# SCH_macropad_2024-06-17.net
KiCad netlist of a schematic drawn in EasyEDA
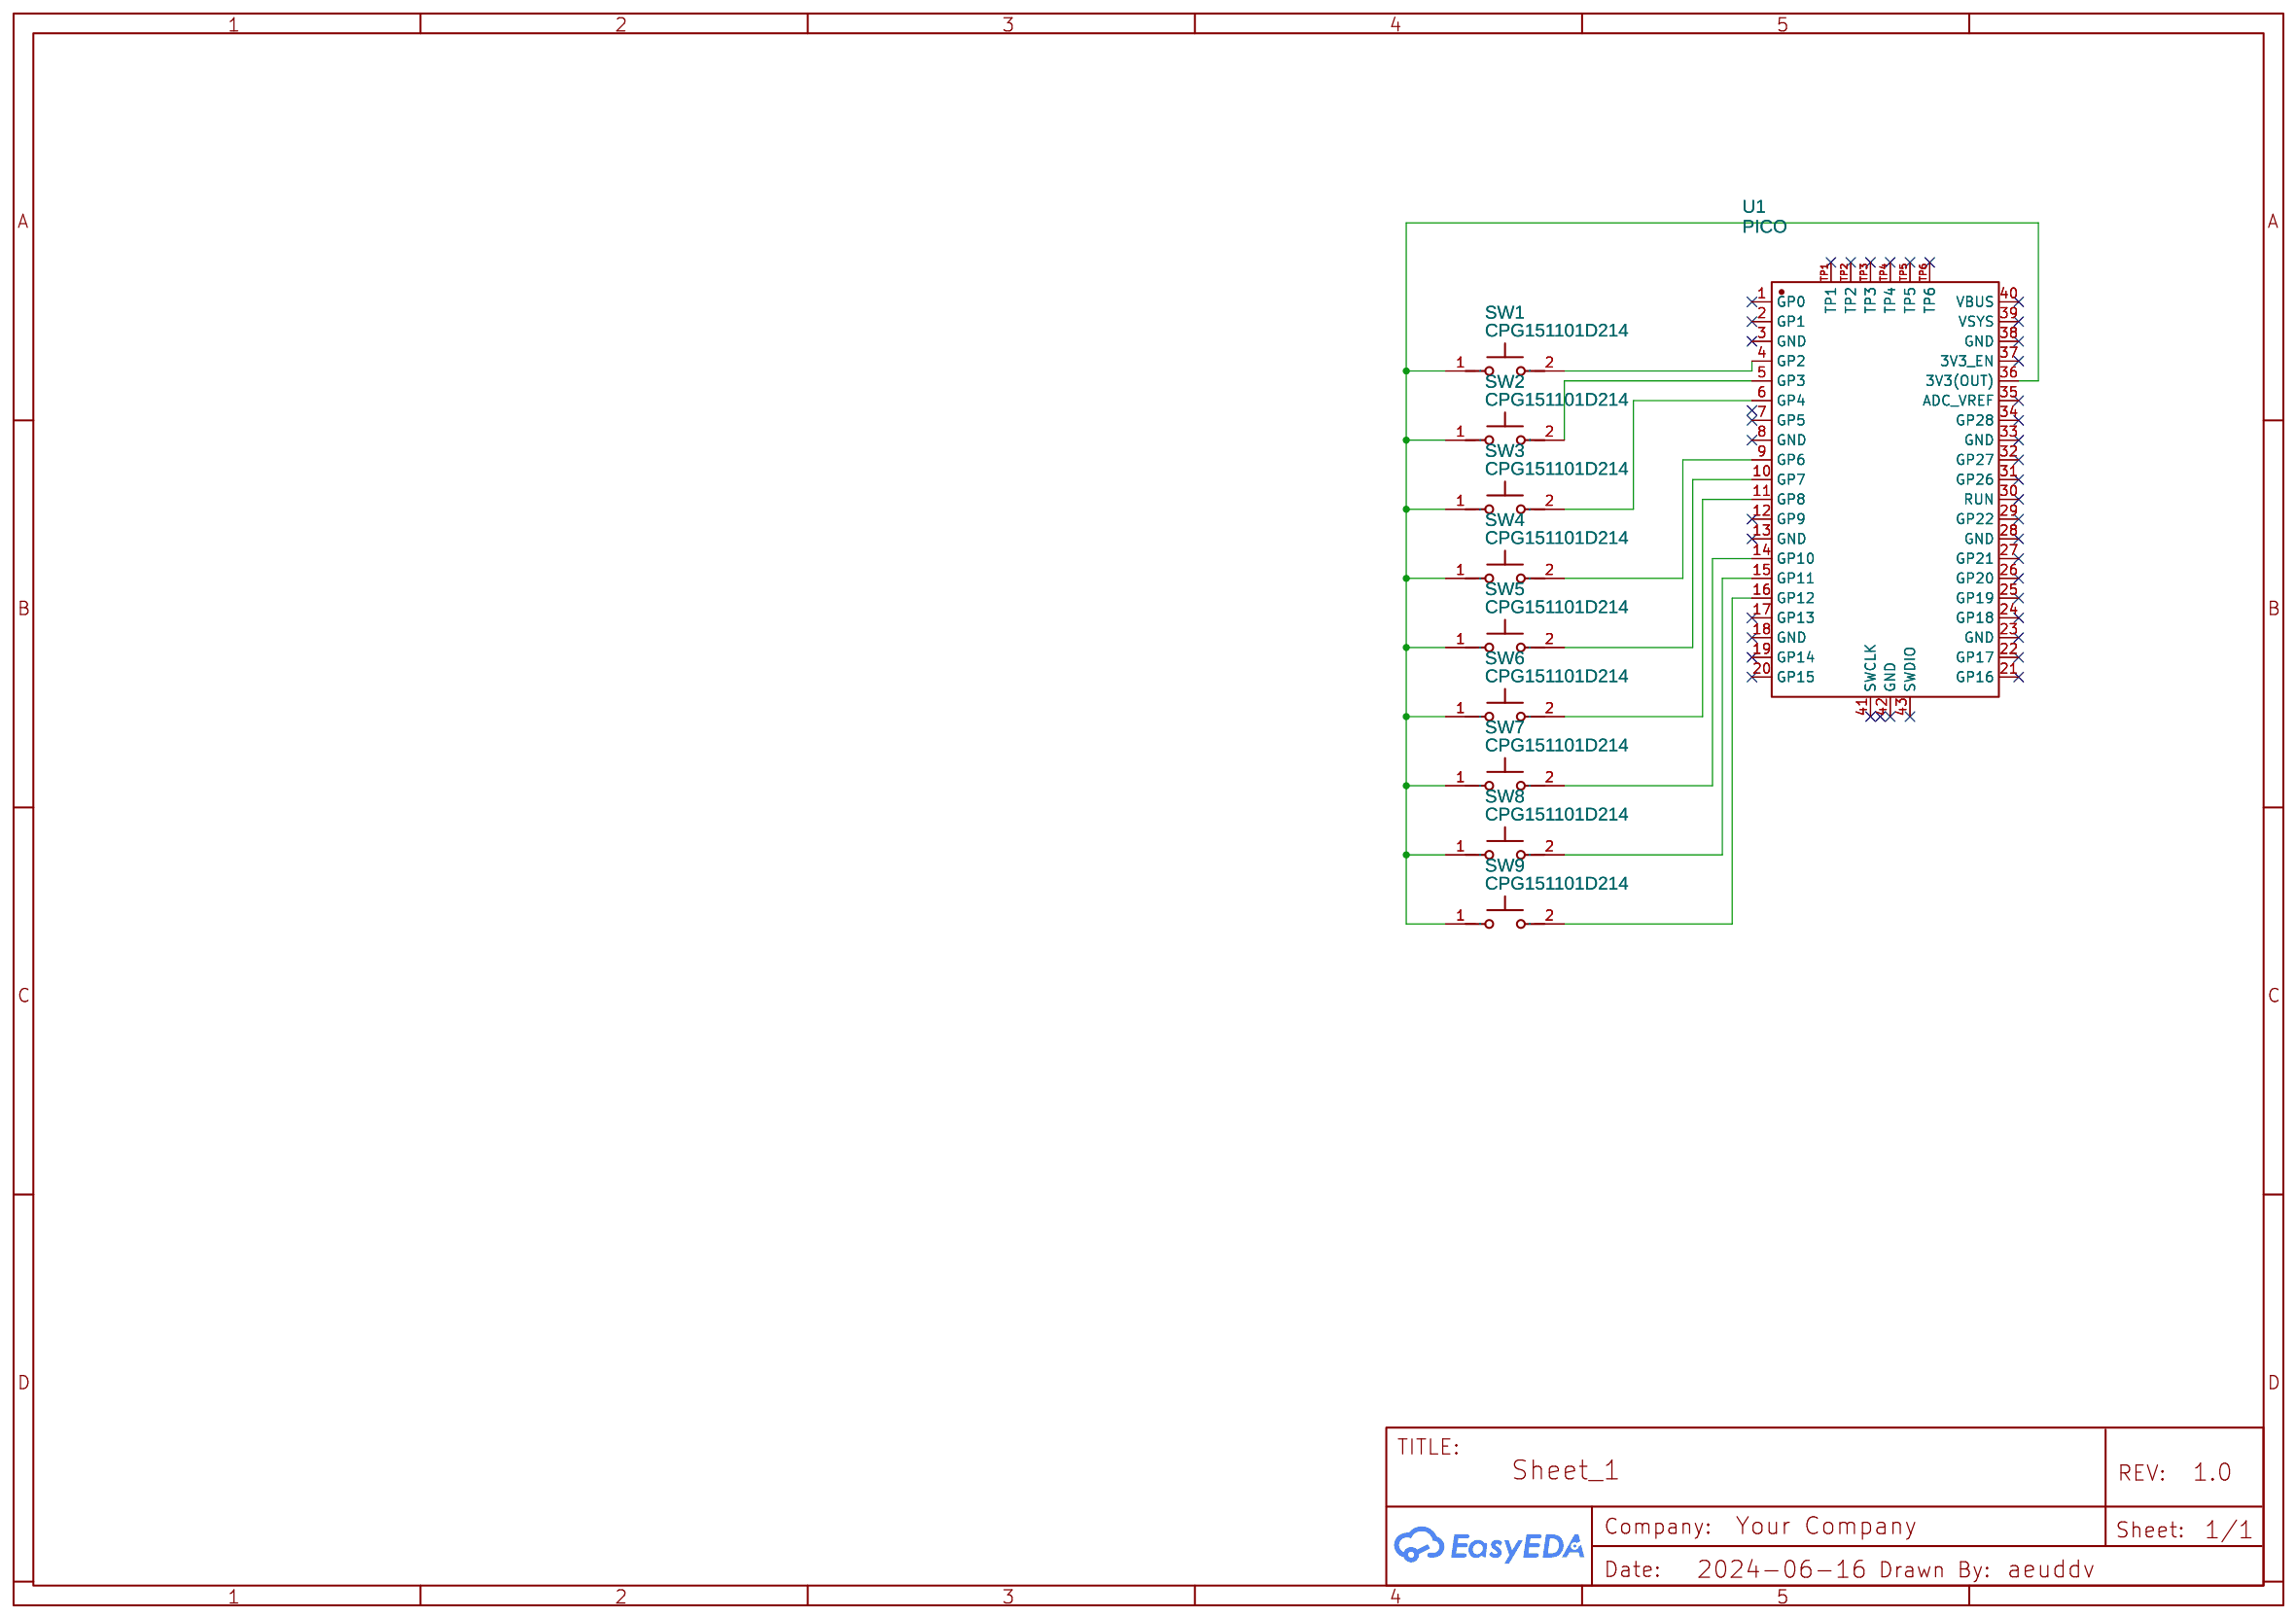
[diagram p0: schematic sheet]

(export (version "E")
  (design (tool "Eeschema 10.0.6"))
  (components
    (comp (ref "SW1")
      (value "CPG151101D214")
      (fields (field (name "Manufacturer") "Kailh(凯华)"))
      (libsource (lib "") (part "CPG151101D214"))
    )
    (comp (ref "SW2")
      (value "CPG151101D214")
      (fields (field (name "Manufacturer") "Kailh(凯华)"))
      (libsource (lib "") (part "CPG151101D214"))
    )
    (comp (ref "SW3")
      (value "CPG151101D214")
      (fields (field (name "Manufacturer") "Kailh(凯华)"))
      (libsource (lib "") (part "CPG151101D214"))
    )
    (comp (ref "SW4")
      (value "CPG151101D214")
      (fields (field (name "Manufacturer") "Kailh(凯华)"))
      (libsource (lib "") (part "CPG151101D214"))
    )
    (comp (ref "SW5")
      (value "CPG151101D214")
      (fields (field (name "Manufacturer") "Kailh(凯华)"))
      (libsource (lib "") (part "CPG151101D214"))
    )
    (comp (ref "SW6")
      (value "CPG151101D214")
      (fields (field (name "Manufacturer") "Kailh(凯华)"))
      (libsource (lib "") (part "CPG151101D214"))
    )
    (comp (ref "SW7")
      (value "CPG151101D214")
      (fields (field (name "Manufacturer") "Kailh(凯华)"))
      (libsource (lib "") (part "CPG151101D214"))
    )
    (comp (ref "SW8")
      (value "CPG151101D214")
      (fields (field (name "Manufacturer") "Kailh(凯华)"))
      (libsource (lib "") (part "CPG151101D214"))
    )
    (comp (ref "SW9")
      (value "CPG151101D214")
      (fields (field (name "Manufacturer") "Kailh(凯华)"))
      (libsource (lib "") (part "CPG151101D214"))
    )
    (comp (ref "U1")
      (value "PICO")
      (fields (field (name "Manufacturer") "Raspberry Pi(树莓派)"))
      (libsource (lib "") (part "PICO"))
    )
  )
  (nets
    (net (code "1") (name "Net-(U1-3V3(OUT))") (class "Default")
      (node (ref "SW1") (pin "1") (pinfunction "1_1") (pintype "unspecified"))
      (node (ref "SW2") (pin "1") (pinfunction "1_1") (pintype "unspecified"))
      (node (ref "SW3") (pin "1") (pinfunction "1_1") (pintype "unspecified"))
      (node (ref "SW4") (pin "1") (pinfunction "1_1") (pintype "unspecified"))
      (node (ref "SW5") (pin "1") (pinfunction "1_1") (pintype "unspecified"))
      (node (ref "SW6") (pin "1") (pinfunction "1_1") (pintype "unspecified"))
      (node (ref "SW7") (pin "1") (pinfunction "1_1") (pintype "unspecified"))
      (node (ref "SW8") (pin "1") (pinfunction "1_1") (pintype "unspecified"))
      (node (ref "SW9") (pin "1") (pinfunction "1_1") (pintype "unspecified"))
      (node (ref "U1") (pin "36") (pinfunction "3V3(OUT)_36") (pintype "unspecified"))
    )
    (net (code "2") (name "Net-(U1-GP2)") (class "Default")
      (node (ref "SW1") (pin "2") (pinfunction "2_2") (pintype "unspecified"))
      (node (ref "U1") (pin "4") (pinfunction "GP2_4") (pintype "unspecified"))
    )
    (net (code "3") (name "Net-(U1-GP3)") (class "Default")
      (node (ref "SW2") (pin "2") (pinfunction "2_2") (pintype "unspecified"))
      (node (ref "U1") (pin "5") (pinfunction "GP3_5") (pintype "unspecified"))
    )
    (net (code "4") (name "Net-(U1-GP4)") (class "Default")
      (node (ref "SW3") (pin "2") (pinfunction "2_2") (pintype "unspecified"))
      (node (ref "U1") (pin "6") (pinfunction "GP4_6") (pintype "unspecified"))
    )
    (net (code "5") (name "Net-(U1-GP6)") (class "Default")
      (node (ref "SW4") (pin "2") (pinfunction "2_2") (pintype "unspecified"))
      (node (ref "U1") (pin "9") (pinfunction "GP6_9") (pintype "unspecified"))
    )
    (net (code "6") (name "Net-(U1-GP7)") (class "Default")
      (node (ref "SW5") (pin "2") (pinfunction "2_2") (pintype "unspecified"))
      (node (ref "U1") (pin "10") (pinfunction "GP7_10") (pintype "unspecified"))
    )
    (net (code "7") (name "Net-(U1-GP8)") (class "Default")
      (node (ref "SW6") (pin "2") (pinfunction "2_2") (pintype "unspecified"))
      (node (ref "U1") (pin "11") (pinfunction "GP8_11") (pintype "unspecified"))
    )
    (net (code "8") (name "Net-(U1-GP10)") (class "Default")
      (node (ref "SW7") (pin "2") (pinfunction "2_2") (pintype "unspecified"))
      (node (ref "U1") (pin "14") (pinfunction "GP10_14") (pintype "unspecified"))
    )
    (net (code "9") (name "Net-(U1-GP11)") (class "Default")
      (node (ref "SW8") (pin "2") (pinfunction "2_2") (pintype "unspecified"))
      (node (ref "U1") (pin "15") (pinfunction "GP11_15") (pintype "unspecified"))
    )
    (net (code "10") (name "Net-(U1-GP12)") (class "Default")
      (node (ref "SW9") (pin "2") (pinfunction "2_2") (pintype "unspecified"))
      (node (ref "U1") (pin "16") (pinfunction "GP12_16") (pintype "unspecified"))
    )
    (net (code "11") (name "unconnected-(U1-3V3_EN-Pad37)") (class "Default")
      (node (ref "U1") (pin "37") (pinfunction "3V3_EN_37") (pintype "unspecified+no_connect"))
    )
    (net (code "12") (name "unconnected-(U1-ADC_VREF-Pad35)") (class "Default")
      (node (ref "U1") (pin "35") (pinfunction "ADC_VREF_35") (pintype "unspecified+no_connect"))
    )
    (net (code "13") (name "unconnected-(U1-GND-Pad3)") (class "Default")
      (node (ref "U1") (pin "3") (pinfunction "GND_3") (pintype "unspecified+no_connect"))
    )
    (net (code "14") (name "unconnected-(U1-GND-Pad8)") (class "Default")
      (node (ref "U1") (pin "8") (pinfunction "GND_8") (pintype "unspecified+no_connect"))
    )
    (net (code "15") (name "unconnected-(U1-GND-Pad13)") (class "Default")
      (node (ref "U1") (pin "13") (pinfunction "GND_13") (pintype "unspecified+no_connect"))
    )
    (net (code "16") (name "unconnected-(U1-GND-Pad18)") (class "Default")
      (node (ref "U1") (pin "18") (pinfunction "GND_18") (pintype "unspecified+no_connect"))
    )
    (net (code "17") (name "unconnected-(U1-GND-Pad23)") (class "Default")
      (node (ref "U1") (pin "23") (pinfunction "GND_23") (pintype "unspecified+no_connect"))
    )
    (net (code "18") (name "unconnected-(U1-GND-Pad28)") (class "Default")
      (node (ref "U1") (pin "28") (pinfunction "GND_28") (pintype "unspecified+no_connect"))
    )
    (net (code "19") (name "unconnected-(U1-GND-Pad33)") (class "Default")
      (node (ref "U1") (pin "33") (pinfunction "GND_33") (pintype "unspecified+no_connect"))
    )
    (net (code "20") (name "unconnected-(U1-GND-Pad38)") (class "Default")
      (node (ref "U1") (pin "38") (pinfunction "GND_38") (pintype "unspecified+no_connect"))
    )
    (net (code "21") (name "unconnected-(U1-GND-Pad42)") (class "Default")
      (node (ref "U1") (pin "42") (pinfunction "GND_42") (pintype "unspecified+no_connect"))
    )
    (net (code "22") (name "unconnected-(U1-GP0-Pad1)") (class "Default")
      (node (ref "U1") (pin "1") (pinfunction "GP0_1") (pintype "unspecified+no_connect"))
    )
    (net (code "23") (name "unconnected-(U1-GP1-Pad2)") (class "Default")
      (node (ref "U1") (pin "2") (pinfunction "GP1_2") (pintype "unspecified+no_connect"))
    )
    (net (code "24") (name "unconnected-(U1-GP5-Pad7)") (class "Default")
      (node (ref "U1") (pin "7") (pinfunction "GP5_7") (pintype "unspecified+no_connect"))
    )
    (net (code "25") (name "unconnected-(U1-GP9-Pad12)") (class "Default")
      (node (ref "U1") (pin "12") (pinfunction "GP9_12") (pintype "unspecified+no_connect"))
    )
    (net (code "26") (name "unconnected-(U1-GP13-Pad17)") (class "Default")
      (node (ref "U1") (pin "17") (pinfunction "GP13_17") (pintype "unspecified+no_connect"))
    )
    (net (code "27") (name "unconnected-(U1-GP14-Pad19)") (class "Default")
      (node (ref "U1") (pin "19") (pinfunction "GP14_19") (pintype "unspecified+no_connect"))
    )
    (net (code "28") (name "unconnected-(U1-GP15-Pad20)") (class "Default")
      (node (ref "U1") (pin "20") (pinfunction "GP15_20") (pintype "unspecified+no_connect"))
    )
    (net (code "29") (name "unconnected-(U1-GP16-Pad21)") (class "Default")
      (node (ref "U1") (pin "21") (pinfunction "GP16_21") (pintype "unspecified+no_connect"))
    )
    (net (code "30") (name "unconnected-(U1-GP17-Pad22)") (class "Default")
      (node (ref "U1") (pin "22") (pinfunction "GP17_22") (pintype "unspecified+no_connect"))
    )
    (net (code "31") (name "unconnected-(U1-GP18-Pad24)") (class "Default")
      (node (ref "U1") (pin "24") (pinfunction "GP18_24") (pintype "unspecified+no_connect"))
    )
    (net (code "32") (name "unconnected-(U1-GP19-Pad25)") (class "Default")
      (node (ref "U1") (pin "25") (pinfunction "GP19_25") (pintype "unspecified+no_connect"))
    )
    (net (code "33") (name "unconnected-(U1-GP20-Pad26)") (class "Default")
      (node (ref "U1") (pin "26") (pinfunction "GP20_26") (pintype "unspecified+no_connect"))
    )
    (net (code "34") (name "unconnected-(U1-GP21-Pad27)") (class "Default")
      (node (ref "U1") (pin "27") (pinfunction "GP21_27") (pintype "unspecified+no_connect"))
    )
    (net (code "35") (name "unconnected-(U1-GP22-Pad29)") (class "Default")
      (node (ref "U1") (pin "29") (pinfunction "GP22_29") (pintype "unspecified+no_connect"))
    )
    (net (code "36") (name "unconnected-(U1-GP26-Pad31)") (class "Default")
      (node (ref "U1") (pin "31") (pinfunction "GP26_31") (pintype "unspecified+no_connect"))
    )
    (net (code "37") (name "unconnected-(U1-GP27-Pad32)") (class "Default")
      (node (ref "U1") (pin "32") (pinfunction "GP27_32") (pintype "unspecified+no_connect"))
    )
    (net (code "38") (name "unconnected-(U1-GP28-Pad34)") (class "Default")
      (node (ref "U1") (pin "34") (pinfunction "GP28_34") (pintype "unspecified+no_connect"))
    )
    (net (code "39") (name "unconnected-(U1-PadTP1)") (class "Default")
      (node (ref "U1") (pin "TP1") (pinfunction "TP1_TP1") (pintype "unspecified+no_connect"))
    )
    (net (code "40") (name "unconnected-(U1-PadTP2)") (class "Default")
      (node (ref "U1") (pin "TP2") (pinfunction "TP2_TP2") (pintype "unspecified+no_connect"))
    )
    (net (code "41") (name "unconnected-(U1-PadTP3)") (class "Default")
      (node (ref "U1") (pin "TP3") (pinfunction "TP3_TP3") (pintype "unspecified+no_connect"))
    )
    (net (code "42") (name "unconnected-(U1-PadTP4)") (class "Default")
      (node (ref "U1") (pin "TP4") (pinfunction "TP4_TP4") (pintype "unspecified+no_connect"))
    )
    (net (code "43") (name "unconnected-(U1-PadTP5)") (class "Default")
      (node (ref "U1") (pin "TP5") (pinfunction "TP5_TP5") (pintype "unspecified+no_connect"))
    )
    (net (code "44") (name "unconnected-(U1-PadTP6)") (class "Default")
      (node (ref "U1") (pin "TP6") (pinfunction "TP6_TP6") (pintype "unspecified+no_connect"))
    )
    (net (code "45") (name "unconnected-(U1-RUN-Pad30)") (class "Default")
      (node (ref "U1") (pin "30") (pinfunction "RUN_30") (pintype "unspecified+no_connect"))
    )
    (net (code "46") (name "unconnected-(U1-SWCLK-Pad41)") (class "Default")
      (node (ref "U1") (pin "41") (pinfunction "SWCLK_41") (pintype "unspecified+no_connect"))
    )
    (net (code "47") (name "unconnected-(U1-SWDIO-Pad43)") (class "Default")
      (node (ref "U1") (pin "43") (pinfunction "SWDIO_43") (pintype "unspecified+no_connect"))
    )
    (net (code "48") (name "unconnected-(U1-VBUS-Pad40)") (class "Default")
      (node (ref "U1") (pin "40") (pinfunction "VBUS_40") (pintype "unspecified+no_connect"))
    )
    (net (code "49") (name "unconnected-(U1-VSYS-Pad39)") (class "Default")
      (node (ref "U1") (pin "39") (pinfunction "VSYS_39") (pintype "unspecified+no_connect"))
    )
  )
)
